# Arduino-lilypad-USB.net
KiCad netlist of a schematic drawn in EAGLE
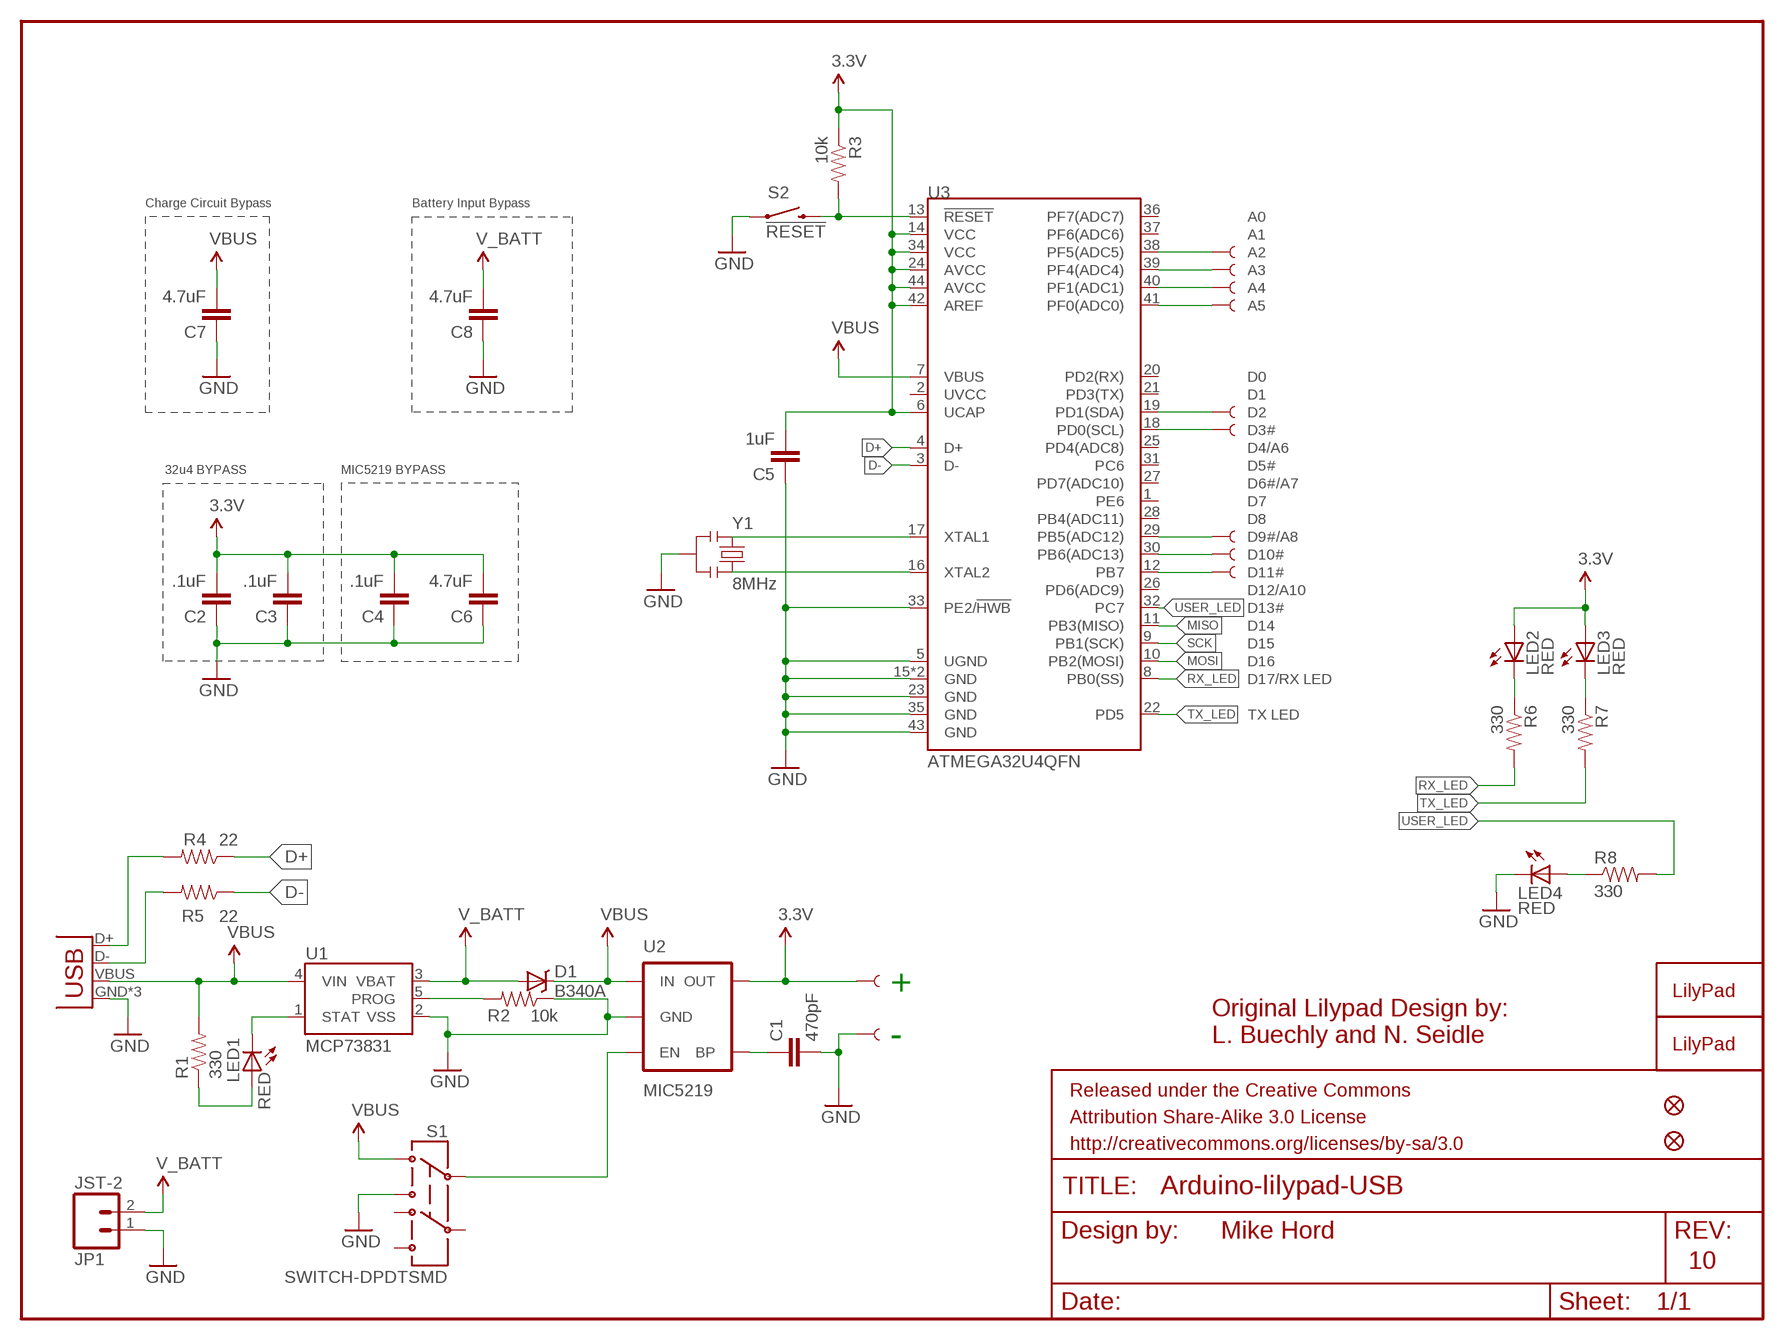
[diagram p0: schematic, sheet 1]

(export (version "E")
  (design (tool "Eeschema 10.0.6"))
  (components
    (comp (ref "+")
      (value "SEWTAP9")
      (footprint "eagle-import:PETAL-LONG-1-2SIDE")
      (fields (field (name "NO_PART") "1"))
      (libsource (lib "eagle-import") (part "SEWTAP9"))
    )
    (comp (ref "-")
      (value "SEWTAP9")
      (footprint "eagle-import:PETAL-LONG-1-2SIDE")
      (fields (field (name "NO_PART") "1"))
      (libsource (lib "eagle-import") (part "SEWTAP9"))
    )
    (comp (ref "A2")
      (value "SEWTAP9")
      (footprint "eagle-import:PETAL-LONG-1-2SIDE")
      (fields (field (name "NO_PART") "1"))
      (libsource (lib "eagle-import") (part "SEWTAP9"))
    )
    (comp (ref "A3")
      (value "SEWTAP9")
      (footprint "eagle-import:PETAL-LONG-1-2SIDE")
      (fields (field (name "NO_PART") "1"))
      (libsource (lib "eagle-import") (part "SEWTAP9"))
    )
    (comp (ref "A4")
      (value "SEWTAP9")
      (footprint "eagle-import:PETAL-LONG-1-2SIDE")
      (fields (field (name "NO_PART") "1"))
      (libsource (lib "eagle-import") (part "SEWTAP9"))
    )
    (comp (ref "A5")
      (value "SEWTAP9")
      (footprint "eagle-import:PETAL-LONG-1-2SIDE")
      (fields (field (name "NO_PART") "1"))
      (libsource (lib "eagle-import") (part "SEWTAP9"))
    )
    (comp (ref "C1")
      (value "470pF")
      (footprint "eagle-import:0603-CAP")
      (libsource (lib "eagle-import") (part "CAP0603-CAP"))
    )
    (comp (ref "C2")
      (value ".1uF")
      (footprint "eagle-import:0603-CAP")
      (libsource (lib "eagle-import") (part "CAP0603-CAP"))
    )
    (comp (ref "C3")
      (value ".1uF")
      (footprint "eagle-import:0603-CAP")
      (libsource (lib "eagle-import") (part "CAP0603-CAP"))
    )
    (comp (ref "C4")
      (value ".1uF")
      (footprint "eagle-import:0603-CAP")
      (libsource (lib "eagle-import") (part "CAP0603-CAP"))
    )
    (comp (ref "C5")
      (value "1uF")
      (footprint "eagle-import:0603-CAP")
      (libsource (lib "eagle-import") (part "CAP0603-CAP"))
    )
    (comp (ref "C6")
      (value "4.7uF")
      (footprint "eagle-import:0603-CAP")
      (libsource (lib "eagle-import") (part "CAP0603-CAP"))
    )
    (comp (ref "C7")
      (value "4.7uF")
      (footprint "eagle-import:1206")
      (libsource (lib "eagle-import") (part "CAP1206"))
    )
    (comp (ref "C8")
      (value "4.7uF")
      (footprint "eagle-import:1206")
      (libsource (lib "eagle-import") (part "CAP1206"))
    )
    (comp (ref "D1")
      (value "B340A")
      (footprint "eagle-import:SMA-DIODE")
      (libsource (lib "eagle-import") (part "DIODE-SCHOTTKY_"))
    )
    (comp (ref "D5")
      (value "SEWTAP9")
      (footprint "eagle-import:PETAL-LONG-1-2SIDE")
      (fields (field (name "NO_PART") "1"))
      (libsource (lib "eagle-import") (part "SEWTAP9"))
    )
    (comp (ref "D6")
      (value "SEWTAP9")
      (footprint "eagle-import:PETAL-LONG-1-2SIDE")
      (fields (field (name "NO_PART") "1"))
      (libsource (lib "eagle-import") (part "SEWTAP9"))
    )
    (comp (ref "D9")
      (value "SEWTAP9")
      (footprint "eagle-import:PETAL-LONG-1-2SIDE")
      (fields (field (name "NO_PART") "1"))
      (libsource (lib "eagle-import") (part "SEWTAP9"))
    )
    (comp (ref "D10")
      (value "SEWTAP9")
      (footprint "eagle-import:PETAL-LONG-1-2SIDE")
      (fields (field (name "NO_PART") "1"))
      (libsource (lib "eagle-import") (part "SEWTAP9"))
    )
    (comp (ref "D11")
      (value "SEWTAP9")
      (footprint "eagle-import:PETAL-LONG-1-2SIDE")
      (fields (field (name "NO_PART") "1"))
      (libsource (lib "eagle-import") (part "SEWTAP9"))
    )
    (comp (ref "JP1")
      (value "JST-2")
      (footprint "eagle-import:JST-2-SMD")
      (libsource (lib "eagle-import") (part "M02-JST-2MM-SMT"))
    )
    (comp (ref "JP2")
      (value "FIDUCIALUFIDUCIAL")
      (footprint "eagle-import:MICRO-FIDUCIAL")
      (libsource (lib "eagle-import") (part "FIDUCIALUFIDUCIAL"))
    )
    (comp (ref "JP3")
      (value "FIDUCIALUFIDUCIAL")
      (footprint "eagle-import:MICRO-FIDUCIAL")
      (libsource (lib "eagle-import") (part "FIDUCIALUFIDUCIAL"))
    )
    (comp (ref "LED1")
      (value "RED")
      (footprint "eagle-import:LED-0603")
      (libsource (lib "eagle-import") (part "LED0603"))
    )
    (comp (ref "LED2")
      (value "RED")
      (footprint "eagle-import:LED-0603")
      (libsource (lib "eagle-import") (part "LED0603"))
    )
    (comp (ref "LED3")
      (value "RED")
      (footprint "eagle-import:LED-0603")
      (libsource (lib "eagle-import") (part "LED0603"))
    )
    (comp (ref "LED4")
      (value "RED")
      (footprint "eagle-import:LED-0603")
      (libsource (lib "eagle-import") (part "LED0603"))
    )
    (comp (ref "R1")
      (value "330")
      (footprint "eagle-import:0603-RES")
      (libsource (lib "eagle-import") (part "RESISTOR0603-RES"))
    )
    (comp (ref "R2")
      (value "10k")
      (footprint "eagle-import:0603-RES")
      (libsource (lib "eagle-import") (part "RESISTOR0603-RES"))
    )
    (comp (ref "R3")
      (value "10k")
      (footprint "eagle-import:0603-RES")
      (libsource (lib "eagle-import") (part "RESISTOR0603-RES"))
    )
    (comp (ref "R4")
      (value "22")
      (footprint "eagle-import:0603-RES")
      (libsource (lib "eagle-import") (part "RESISTOR0603-RES"))
    )
    (comp (ref "R5")
      (value "22")
      (footprint "eagle-import:0603-RES")
      (libsource (lib "eagle-import") (part "RESISTOR0603-RES"))
    )
    (comp (ref "R6")
      (value "330")
      (footprint "eagle-import:0603-RES")
      (libsource (lib "eagle-import") (part "RESISTOR0603-RES"))
    )
    (comp (ref "R7")
      (value "330")
      (footprint "eagle-import:0603-RES")
      (libsource (lib "eagle-import") (part "RESISTOR0603-RES"))
    )
    (comp (ref "R8")
      (value "330")
      (footprint "eagle-import:0603-RES")
      (libsource (lib "eagle-import") (part "RESISTOR0603-RES"))
    )
    (comp (ref "S1")
      (value "SWITCH-DPDTSMD")
      (footprint "eagle-import:AYZ0202")
      (libsource (lib "eagle-import") (part "SWITCH-DPDTSMD"))
    )
    (comp (ref "S2")
      (value "!RESET")
      (footprint "eagle-import:TACTILE_SWITCH_SMD")
      (libsource (lib "eagle-import") (part "SWITCH-MOMENTARY-2SMD"))
    )
    (comp (ref "U$1")
      (value "LOGO-LPLPA")
      (footprint "eagle-import:LOGO-LPA")
      (libsource (lib "eagle-import") (part "LOGO-LPLPA"))
    )
    (comp (ref "U$13")
      (value "LOGO-LPLP")
      (footprint "eagle-import:LOGO-LILYPAD")
      (fields (field (name "NO_PART") "1"))
      (libsource (lib "eagle-import") (part "LOGO-LPLP"))
    )
    (comp (ref "U1")
      (value "MCP73831")
      (footprint "eagle-import:SOT23-5")
      (libsource (lib "eagle-import") (part "MCP73831"))
    )
    (comp (ref "U2")
      (value "MIC5219")
      (footprint "eagle-import:SOT23-5")
      (libsource (lib "eagle-import") (part "V_REG_MIC5219SMD"))
    )
    (comp (ref "U3")
      (value "ATMEGA32U4QFN")
      (footprint "eagle-import:QFN-44")
      (libsource (lib "eagle-import") (part "ATMEGA32U4QFN"))
    )
    (comp (ref "X1")
      (value "USB-MICROB")
      (footprint "eagle-import:USB-MICROB")
      (libsource (lib "eagle-import") (part "USB-MICROB"))
    )
    (comp (ref "Y1")
      (value "8MHz")
      (footprint "eagle-import:RESONATOR-SMD")
      (libsource (lib "eagle-import") (part "RESONATORSMD"))
    )
  )
  (nets
    (net (code "1") (name "3.3V") (class "Default")
      (node (ref "+") (pin "1") (pinfunction "1_1") (pintype "bidirectional"))
      (node (ref "C2") (pin "2") (pinfunction "2_2") (pintype "passive"))
      (node (ref "C3") (pin "2") (pinfunction "2_2") (pintype "passive"))
      (node (ref "C4") (pin "2") (pinfunction "2_2") (pintype "passive"))
      (node (ref "C5") (pin "2") (pinfunction "2_2") (pintype "passive"))
      (node (ref "C6") (pin "2") (pinfunction "2_2") (pintype "passive"))
      (node (ref "LED2") (pin "A") (pinfunction "A_A") (pintype "passive"))
      (node (ref "LED3") (pin "A") (pinfunction "A_A") (pintype "passive"))
      (node (ref "R3") (pin "1") (pinfunction "1_1") (pintype "passive"))
      (node (ref "U2") (pin "5") (pinfunction "OUT_5") (pintype "passive"))
      (node (ref "U3") (pin "14") (pinfunction "VCC_14") (pintype "bidirectional"))
      (node (ref "U3") (pin "24") (pinfunction "AVCC_24") (pintype "bidirectional"))
      (node (ref "U3") (pin "34") (pinfunction "VCC_34") (pintype "bidirectional"))
      (node (ref "U3") (pin "42") (pinfunction "AREF_42") (pintype "bidirectional"))
      (node (ref "U3") (pin "44") (pinfunction "AVCC_44") (pintype "bidirectional"))
      (node (ref "U3") (pin "6") (pinfunction "UCAP_6") (pintype "bidirectional"))
    )
    (net (code "2") (name "D+") (class "Default")
      (node (ref "R4") (pin "1") (pinfunction "1_1") (pintype "passive"))
      (node (ref "U3") (pin "4") (pinfunction "D+_4") (pintype "bidirectional"))
    )
    (net (code "3") (name "D-") (class "Default")
      (node (ref "R5") (pin "1") (pinfunction "1_1") (pintype "passive"))
      (node (ref "U3") (pin "3") (pinfunction "D-_3") (pintype "bidirectional"))
    )
    (net (code "4") (name "GND") (class "Default")
      (node (ref "-") (pin "1") (pinfunction "1_1") (pintype "bidirectional"))
      (node (ref "C1") (pin "2") (pinfunction "2_2") (pintype "passive"))
      (node (ref "C2") (pin "1") (pinfunction "1_1") (pintype "passive"))
      (node (ref "C3") (pin "1") (pinfunction "1_1") (pintype "passive"))
      (node (ref "C4") (pin "1") (pinfunction "1_1") (pintype "passive"))
      (node (ref "C5") (pin "1") (pinfunction "1_1") (pintype "passive"))
      (node (ref "C6") (pin "1") (pinfunction "1_1") (pintype "passive"))
      (node (ref "C7") (pin "1") (pinfunction "1_1") (pintype "passive"))
      (node (ref "C8") (pin "1") (pinfunction "1_1") (pintype "passive"))
      (node (ref "JP1") (pin "1") (pinfunction "2_1") (pintype "passive"))
      (node (ref "LED4") (pin "C") (pinfunction "C_C") (pintype "passive"))
      (node (ref "R2") (pin "1") (pinfunction "1_1") (pintype "passive"))
      (node (ref "S1") (pin "3") (pinfunction "3_3") (pintype "bidirectional"))
      (node (ref "S2") (pin "1") (pinfunction "1_1") (pintype "passive"))
      (node (ref "U1") (pin "2") (pinfunction "VSS_2") (pintype "power_in"))
      (node (ref "U2") (pin "2") (pinfunction "GND_2") (pintype "input"))
      (node (ref "U3") (pin "15") (pinfunction "GND_15") (pintype "bidirectional"))
      (node (ref "U3") (pin "23") (pinfunction "GND_23") (pintype "bidirectional"))
      (node (ref "U3") (pin "33") (pinfunction "PE2/~{HWB}_33") (pintype "bidirectional"))
      (node (ref "U3") (pin "35") (pinfunction "GND_35") (pintype "bidirectional"))
      (node (ref "U3") (pin "43") (pinfunction "GND_43") (pintype "bidirectional"))
      (node (ref "U3") (pin "5") (pinfunction "UGND_5") (pintype "bidirectional"))
      (node (ref "U3") (pin "EPAD") (pinfunction "GND_EPAD") (pintype "bidirectional"))
      (node (ref "X1") (pin "GND") (pinfunction "GND_GND") (pintype "bidirectional"))
      (node (ref "X1") (pin "MT1") (pinfunction "GND_MT1") (pintype "bidirectional"))
      (node (ref "X1") (pin "MT2") (pinfunction "GND_MT2") (pintype "bidirectional"))
      (node (ref "Y1") (pin "2") (pinfunction "2_2") (pintype "passive"))
    )
    (net (code "5") (name "MISO") (class "Default")
      (node (ref "U3") (pin "11") (pinfunction "PB3(MISO)_11") (pintype "bidirectional"))
    )
    (net (code "6") (name "MOSI") (class "Default")
      (node (ref "U3") (pin "10") (pinfunction "PB2(MOSI)_10") (pintype "bidirectional"))
    )
    (net (code "7") (name "Net-(LED1-PadA)") (class "Default")
      (node (ref "LED1") (pin "A") (pinfunction "A_A") (pintype "passive"))
      (node (ref "R1") (pin "1") (pinfunction "1_1") (pintype "passive"))
    )
    (net (code "8") (name "Net-(LED2-PadC)") (class "Default")
      (node (ref "LED2") (pin "C") (pinfunction "C_C") (pintype "passive"))
      (node (ref "R6") (pin "1") (pinfunction "1_1") (pintype "passive"))
    )
    (net (code "9") (name "Net-(LED3-PadC)") (class "Default")
      (node (ref "LED3") (pin "C") (pinfunction "C_C") (pintype "passive"))
      (node (ref "R7") (pin "1") (pinfunction "1_1") (pintype "passive"))
    )
    (net (code "10") (name "Net-(LED4-PadA)") (class "Default")
      (node (ref "LED4") (pin "A") (pinfunction "A_A") (pintype "passive"))
      (node (ref "R8") (pin "1") (pinfunction "1_1") (pintype "passive"))
    )
    (net (code "11") (name "Net-(R4-Pad2)") (class "Default")
      (node (ref "R4") (pin "2") (pinfunction "2_2") (pintype "passive"))
      (node (ref "X1") (pin "D+") (pinfunction "D+_D+") (pintype "bidirectional"))
    )
    (net (code "12") (name "Net-(R5-Pad2)") (class "Default")
      (node (ref "R5") (pin "2") (pinfunction "2_2") (pintype "passive"))
      (node (ref "X1") (pin "D-") (pinfunction "D-_D-") (pintype "bidirectional"))
    )
    (net (code "13") (name "Net-(S2-2)") (class "Default")
      (node (ref "R3") (pin "2") (pinfunction "2_2") (pintype "passive"))
      (node (ref "S2") (pin "3") (pinfunction "2_3") (pintype "passive"))
      (node (ref "U3") (pin "13") (pinfunction "~{RESET}_13") (pintype "bidirectional"))
    )
    (net (code "14") (name "Net-(U1-PROG)") (class "Default")
      (node (ref "R2") (pin "2") (pinfunction "2_2") (pintype "passive"))
      (node (ref "U1") (pin "5") (pinfunction "PROG_5") (pintype "input"))
    )
    (net (code "15") (name "Net-(U1-STAT)") (class "Default")
      (node (ref "LED1") (pin "C") (pinfunction "C_C") (pintype "passive"))
      (node (ref "U1") (pin "1") (pinfunction "STAT_1") (pintype "output"))
    )
    (net (code "16") (name "Net-(U2-BP)") (class "Default")
      (node (ref "C1") (pin "1") (pinfunction "1_1") (pintype "passive"))
      (node (ref "U2") (pin "4") (pinfunction "BP_4") (pintype "input"))
    )
    (net (code "17") (name "Net-(U2-EN)") (class "Default")
      (node (ref "S1") (pin "2") (pinfunction "2_2") (pintype "bidirectional"))
      (node (ref "U2") (pin "3") (pinfunction "EN_3") (pintype "input"))
    )
    (net (code "18") (name "Net-(U3-PB5(ADC12))") (class "Default")
      (node (ref "D9") (pin "1") (pinfunction "1_1") (pintype "bidirectional"))
      (node (ref "U3") (pin "29") (pinfunction "PB5(ADC12)_29") (pintype "bidirectional"))
    )
    (net (code "19") (name "Net-(U3-PB6(ADC13))") (class "Default")
      (node (ref "D10") (pin "1") (pinfunction "1_1") (pintype "bidirectional"))
      (node (ref "U3") (pin "30") (pinfunction "PB6(ADC13)_30") (pintype "bidirectional"))
    )
    (net (code "20") (name "Net-(U3-PB7)") (class "Default")
      (node (ref "D11") (pin "1") (pinfunction "1_1") (pintype "bidirectional"))
      (node (ref "U3") (pin "12") (pinfunction "PB7_12") (pintype "bidirectional"))
    )
    (net (code "21") (name "Net-(U3-PD0(SCL))") (class "Default")
      (node (ref "D6") (pin "1") (pinfunction "1_1") (pintype "bidirectional"))
      (node (ref "U3") (pin "18") (pinfunction "PD0(SCL)_18") (pintype "bidirectional"))
    )
    (net (code "22") (name "Net-(U3-PD1(SDA))") (class "Default")
      (node (ref "D5") (pin "1") (pinfunction "1_1") (pintype "bidirectional"))
      (node (ref "U3") (pin "19") (pinfunction "PD1(SDA)_19") (pintype "bidirectional"))
    )
    (net (code "23") (name "Net-(U3-PF0(ADC0))") (class "Default")
      (node (ref "A5") (pin "1") (pinfunction "1_1") (pintype "bidirectional"))
      (node (ref "U3") (pin "41") (pinfunction "PF0(ADC0)_41") (pintype "bidirectional"))
    )
    (net (code "24") (name "Net-(U3-PF1(ADC1))") (class "Default")
      (node (ref "A4") (pin "1") (pinfunction "1_1") (pintype "bidirectional"))
      (node (ref "U3") (pin "40") (pinfunction "PF1(ADC1)_40") (pintype "bidirectional"))
    )
    (net (code "25") (name "Net-(U3-PF4(ADC4))") (class "Default")
      (node (ref "A3") (pin "1") (pinfunction "1_1") (pintype "bidirectional"))
      (node (ref "U3") (pin "39") (pinfunction "PF4(ADC4)_39") (pintype "bidirectional"))
    )
    (net (code "26") (name "Net-(U3-PF5(ADC5))") (class "Default")
      (node (ref "A2") (pin "1") (pinfunction "1_1") (pintype "bidirectional"))
      (node (ref "U3") (pin "38") (pinfunction "PF5(ADC5)_38") (pintype "bidirectional"))
    )
    (net (code "27") (name "Net-(U3-XTAL1)") (class "Default")
      (node (ref "U3") (pin "17") (pinfunction "XTAL1_17") (pintype "bidirectional"))
      (node (ref "Y1") (pin "1") (pinfunction "1_1") (pintype "passive"))
    )
    (net (code "28") (name "Net-(U3-XTAL2)") (class "Default")
      (node (ref "U3") (pin "16") (pinfunction "XTAL2_16") (pintype "bidirectional"))
      (node (ref "Y1") (pin "3") (pinfunction "3_3") (pintype "passive"))
    )
    (net (code "29") (name "RX_LED") (class "Default")
      (node (ref "R6") (pin "2") (pinfunction "2_2") (pintype "passive"))
      (node (ref "U3") (pin "8") (pinfunction "PB0(SS)_8") (pintype "bidirectional"))
    )
    (net (code "30") (name "SCK") (class "Default")
      (node (ref "U3") (pin "9") (pinfunction "PB1(SCK)_9") (pintype "bidirectional"))
    )
    (net (code "31") (name "TX_LED") (class "Default")
      (node (ref "R7") (pin "2") (pinfunction "2_2") (pintype "passive"))
      (node (ref "U3") (pin "22") (pinfunction "PD5_22") (pintype "bidirectional"))
    )
    (net (code "32") (name "USER_LED") (class "Default")
      (node (ref "R8") (pin "2") (pinfunction "2_2") (pintype "passive"))
      (node (ref "U3") (pin "32") (pinfunction "PC7_32") (pintype "bidirectional"))
    )
    (net (code "33") (name "VBUS") (class "Default")
      (node (ref "C7") (pin "2") (pinfunction "2_2") (pintype "passive"))
      (node (ref "D1") (pin "C") (pinfunction "C_C") (pintype "passive"))
      (node (ref "R1") (pin "2") (pinfunction "2_2") (pintype "passive"))
      (node (ref "S1") (pin "1") (pinfunction "1_1") (pintype "bidirectional"))
      (node (ref "U1") (pin "4") (pinfunction "VIN_4") (pintype "power_in"))
      (node (ref "U2") (pin "1") (pinfunction "IN_1") (pintype "input"))
      (node (ref "U3") (pin "7") (pinfunction "VBUS_7") (pintype "bidirectional"))
      (node (ref "X1") (pin "VBUS") (pinfunction "VBUS_VBUS") (pintype "bidirectional"))
    )
    (net (code "34") (name "V_BATT") (class "Default")
      (node (ref "C8") (pin "2") (pinfunction "2_2") (pintype "passive"))
      (node (ref "D1") (pin "A") (pinfunction "A_A") (pintype "passive"))
      (node (ref "JP1") (pin "2") (pinfunction "1_2") (pintype "passive"))
      (node (ref "U1") (pin "3") (pinfunction "VBAT_3") (pintype "power_in"))
    )
    (net (code "35") (name "unconnected-(S1-Pad4)") (class "Default")
      (node (ref "S1") (pin "4") (pinfunction "4_4") (pintype "bidirectional"))
    )
    (net (code "36") (name "unconnected-(S1-Pad5)") (class "Default")
      (node (ref "S1") (pin "5") (pinfunction "5_5") (pintype "bidirectional"))
    )
    (net (code "37") (name "unconnected-(S1-Pad6)") (class "Default")
      (node (ref "S1") (pin "6") (pinfunction "6_6") (pintype "bidirectional"))
    )
    (net (code "38") (name "unconnected-(U3-PB4(ADC11)-Pad28)") (class "Default")
      (node (ref "U3") (pin "28") (pinfunction "PB4(ADC11)_28") (pintype "bidirectional"))
    )
    (net (code "39") (name "unconnected-(U3-PC6-Pad31)") (class "Default")
      (node (ref "U3") (pin "31") (pinfunction "PC6_31") (pintype "bidirectional"))
    )
    (net (code "40") (name "unconnected-(U3-PD2(RX)-Pad20)") (class "Default")
      (node (ref "U3") (pin "20") (pinfunction "PD2(RX)_20") (pintype "bidirectional"))
    )
    (net (code "41") (name "unconnected-(U3-PD3(TX)-Pad21)") (class "Default")
      (node (ref "U3") (pin "21") (pinfunction "PD3(TX)_21") (pintype "bidirectional"))
    )
    (net (code "42") (name "unconnected-(U3-PD4(ADC8)-Pad25)") (class "Default")
      (node (ref "U3") (pin "25") (pinfunction "PD4(ADC8)_25") (pintype "bidirectional"))
    )
    (net (code "43") (name "unconnected-(U3-PD6(ADC9)-Pad26)") (class "Default")
      (node (ref "U3") (pin "26") (pinfunction "PD6(ADC9)_26") (pintype "bidirectional"))
    )
    (net (code "44") (name "unconnected-(U3-PD7(ADC10)-Pad27)") (class "Default")
      (node (ref "U3") (pin "27") (pinfunction "PD7(ADC10)_27") (pintype "bidirectional"))
    )
    (net (code "45") (name "unconnected-(U3-PE6-Pad1)") (class "Default")
      (node (ref "U3") (pin "1") (pinfunction "PE6_1") (pintype "bidirectional"))
    )
    (net (code "46") (name "unconnected-(U3-PF6(ADC6)-Pad37)") (class "Default")
      (node (ref "U3") (pin "37") (pinfunction "PF6(ADC6)_37") (pintype "bidirectional"))
    )
    (net (code "47") (name "unconnected-(U3-PF7(ADC7)-Pad36)") (class "Default")
      (node (ref "U3") (pin "36") (pinfunction "PF7(ADC7)_36") (pintype "bidirectional"))
    )
    (net (code "48") (name "unconnected-(U3-UVCC-Pad2)") (class "Default")
      (node (ref "U3") (pin "2") (pinfunction "UVCC_2") (pintype "bidirectional"))
    )
  )
)
